# schematic.net
KiCad netlist of a schematic drawn in EasyEDA
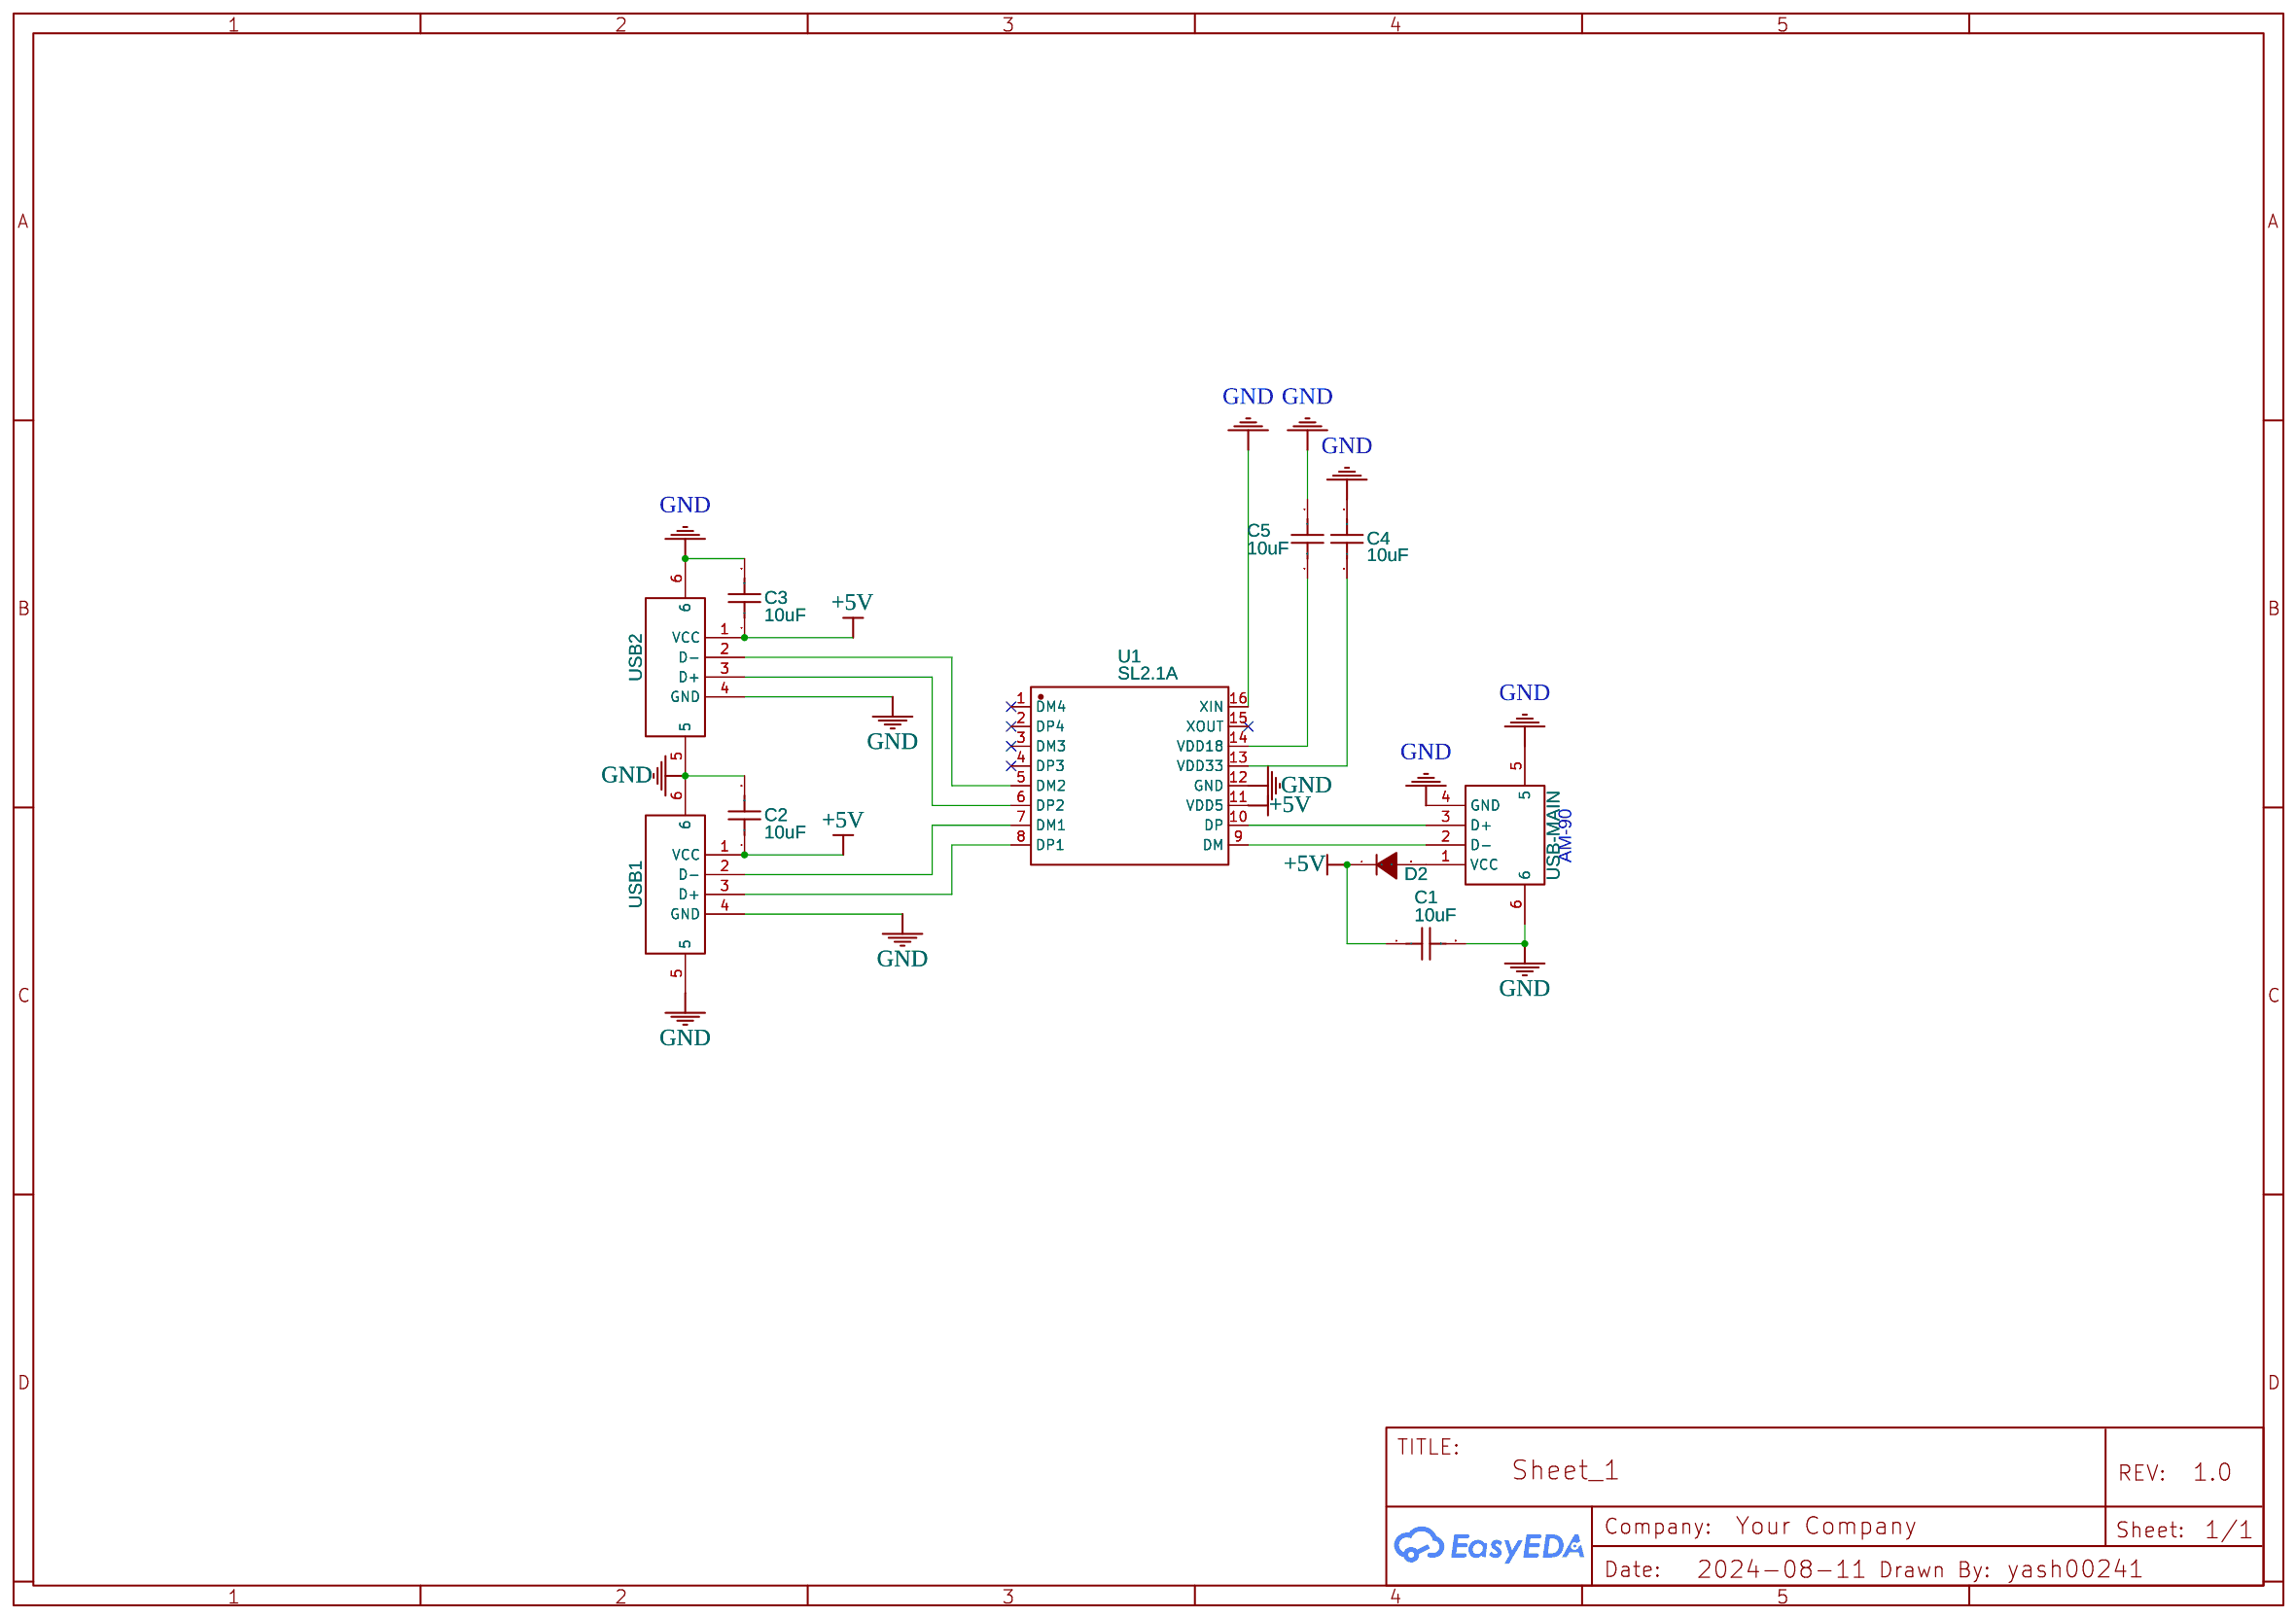
[diagram p0: schematic sheet]

(export (version "E")
  (design (tool "Eeschema 10.0.6"))
  (components
    (comp (ref "C1")
      (value "10uF")
      (fields
        (field (name "Manufacturer Part") "CL10A106KP8NNNC")
        (field (name "Manufacturer") "SAMSUNG(三星)")
      )
      (libsource (lib "") (part "CL10A106KP8NNNC_2"))
    )
    (comp (ref "C2")
      (value "10uF")
      (fields
        (field (name "Manufacturer Part") "CL10A106KP8NNNC")
        (field (name "Manufacturer") "SAMSUNG(三星)")
      )
      (libsource (lib "") (part "CL10A106KP8NNNC_1"))
    )
    (comp (ref "C3")
      (value "10uF")
      (fields
        (field (name "Manufacturer Part") "CL10A106KP8NNNC")
        (field (name "Manufacturer") "SAMSUNG(三星)")
      )
      (libsource (lib "") (part "CL10A106KP8NNNC_1"))
    )
    (comp (ref "C4")
      (value "10uF")
      (fields
        (field (name "Manufacturer Part") "CL10A106KP8NNNC")
        (field (name "Manufacturer") "SAMSUNG(三星)")
      )
      (libsource (lib "") (part "CL10A106KP8NNNC"))
    )
    (comp (ref "C5")
      (value "10uF")
      (fields
        (field (name "Manufacturer Part") "CL10A106KP8NNNC")
        (field (name "Manufacturer") "SAMSUNG(三星)")
      )
      (libsource (lib "") (part "CL10A106KP8NNNC"))
    )
    (comp (ref "D2")
      (value "NSR0320MW2T1G")
      (fields (field (name "Manufacturer") "onsemi(安森美)"))
      (libsource (lib "") (part "NSR0320MW2T1G"))
    )
    (comp (ref "U1")
      (value "SL2.1A")
      (fields (field (name "Manufacturer") "CoreChips(和芯润德)"))
      (libsource (lib "") (part "SL2.1A"))
    )
    (comp (ref "USB-MAIN")
      (value "U-G-04DD-W-01")
      (fields (field (name "Manufacturer Part") "U-G-O4DD-W-1") (field (name "Manufacturer") "韩国韩荣"))
      (libsource (lib "") (part "U-G-04DD-W-01"))
    )
    (comp (ref "USB1")
      (value "Secondary-USB2")
      (fields (field (name "Manufacturer Part") "903-131A1011D10100") (field (name "Manufacturer") "精拓金"))
      (libsource (lib "") (part "USB-AF-90-14.4X13.6-H7.0-DIP"))
    )
    (comp (ref "USB2")
      (value "Seconday-usb1")
      (fields (field (name "Manufacturer Part") "903-131A1011D10100") (field (name "Manufacturer") "精拓金"))
      (libsource (lib "") (part "USB-AF-90-14.4X13.6-H7.0-DIP"))
    )
  )
  (nets
    (net (code "1") (name "+5V") (class "Default")
      (node (ref "C1") (pin "1") (pinfunction "1_1") (pintype "unspecified"))
      (node (ref "C2") (pin "1") (pinfunction "1_1") (pintype "unspecified"))
      (node (ref "C3") (pin "1") (pinfunction "1_1") (pintype "unspecified"))
      (node (ref "D2") (pin "1") (pinfunction "C_1") (pintype "unspecified"))
      (node (ref "U1") (pin "11") (pinfunction "VDD5_11") (pintype "unspecified"))
      (node (ref "USB1") (pin "1") (pinfunction "VCC_1") (pintype "unspecified"))
      (node (ref "USB2") (pin "1") (pinfunction "VCC_1") (pintype "unspecified"))
    )
    (net (code "2") (name "GND") (class "Default")
      (node (ref "C1") (pin "2") (pinfunction "2_2") (pintype "unspecified"))
      (node (ref "C2") (pin "2") (pinfunction "2_2") (pintype "unspecified"))
      (node (ref "C3") (pin "2") (pinfunction "2_2") (pintype "unspecified"))
      (node (ref "C4") (pin "1") (pinfunction "1_1") (pintype "unspecified"))
      (node (ref "C5") (pin "1") (pinfunction "1_1") (pintype "unspecified"))
      (node (ref "U1") (pin "12") (pinfunction "GND_12") (pintype "unspecified"))
      (node (ref "U1") (pin "16") (pinfunction "XIN_16") (pintype "unspecified"))
      (node (ref "USB-MAIN") (pin "4") (pinfunction "GND_4") (pintype "unspecified"))
      (node (ref "USB-MAIN") (pin "5") (pinfunction "5_5") (pintype "unspecified"))
      (node (ref "USB-MAIN") (pin "6") (pinfunction "6_6") (pintype "unspecified"))
      (node (ref "USB1") (pin "4") (pinfunction "GND_4") (pintype "unspecified"))
      (node (ref "USB1") (pin "5") (pinfunction "5_5") (pintype "unspecified"))
      (node (ref "USB1") (pin "6") (pinfunction "6_6") (pintype "unspecified"))
      (node (ref "USB2") (pin "4") (pinfunction "GND_4") (pintype "unspecified"))
      (node (ref "USB2") (pin "5") (pinfunction "5_5") (pintype "unspecified"))
      (node (ref "USB2") (pin "6") (pinfunction "6_6") (pintype "unspecified"))
    )
    (net (code "3") (name "Net-(D2-A)") (class "Default")
      (node (ref "D2") (pin "2") (pinfunction "A_2") (pintype "unspecified"))
      (node (ref "USB-MAIN") (pin "1") (pinfunction "VCC_1") (pintype "unspecified"))
    )
    (net (code "4") (name "Net-(U1-DM)") (class "Default")
      (node (ref "U1") (pin "9") (pinfunction "DM_9") (pintype "unspecified"))
      (node (ref "USB-MAIN") (pin "2") (pinfunction "D-_2") (pintype "unspecified"))
    )
    (net (code "5") (name "Net-(U1-DM1)") (class "Default")
      (node (ref "U1") (pin "7") (pinfunction "DM1_7") (pintype "unspecified"))
      (node (ref "USB1") (pin "2") (pinfunction "D-_2") (pintype "unspecified"))
    )
    (net (code "6") (name "Net-(U1-DM2)") (class "Default")
      (node (ref "U1") (pin "5") (pinfunction "DM2_5") (pintype "unspecified"))
      (node (ref "USB2") (pin "2") (pinfunction "D-_2") (pintype "unspecified"))
    )
    (net (code "7") (name "Net-(U1-DP)") (class "Default")
      (node (ref "U1") (pin "10") (pinfunction "DP_10") (pintype "unspecified"))
      (node (ref "USB-MAIN") (pin "3") (pinfunction "D+_3") (pintype "unspecified"))
    )
    (net (code "8") (name "Net-(U1-DP1)") (class "Default")
      (node (ref "U1") (pin "8") (pinfunction "DP1_8") (pintype "unspecified"))
      (node (ref "USB1") (pin "3") (pinfunction "D+_3") (pintype "unspecified"))
    )
    (net (code "9") (name "Net-(U1-DP2)") (class "Default")
      (node (ref "U1") (pin "6") (pinfunction "DP2_6") (pintype "unspecified"))
      (node (ref "USB2") (pin "3") (pinfunction "D+_3") (pintype "unspecified"))
    )
    (net (code "10") (name "Net-(U1-VDD18)") (class "Default")
      (node (ref "C5") (pin "2") (pinfunction "2_2") (pintype "unspecified"))
      (node (ref "U1") (pin "14") (pinfunction "VDD18_14") (pintype "unspecified"))
    )
    (net (code "11") (name "Net-(U1-VDD33)") (class "Default")
      (node (ref "C4") (pin "2") (pinfunction "2_2") (pintype "unspecified"))
      (node (ref "U1") (pin "13") (pinfunction "VDD33_13") (pintype "unspecified"))
    )
    (net (code "12") (name "unconnected-(U1-DM3-Pad3)") (class "Default")
      (node (ref "U1") (pin "3") (pinfunction "DM3_3") (pintype "unspecified+no_connect"))
    )
    (net (code "13") (name "unconnected-(U1-DM4-Pad1)") (class "Default")
      (node (ref "U1") (pin "1") (pinfunction "DM4_1") (pintype "unspecified+no_connect"))
    )
    (net (code "14") (name "unconnected-(U1-DP3-Pad4)") (class "Default")
      (node (ref "U1") (pin "4") (pinfunction "DP3_4") (pintype "unspecified+no_connect"))
    )
    (net (code "15") (name "unconnected-(U1-DP4-Pad2)") (class "Default")
      (node (ref "U1") (pin "2") (pinfunction "DP4_2") (pintype "unspecified+no_connect"))
    )
    (net (code "16") (name "unconnected-(U1-XOUT-Pad15)") (class "Default")
      (node (ref "U1") (pin "15") (pinfunction "XOUT_15") (pintype "unspecified+no_connect"))
    )
  )
)
